# AVR_Board_4_0_FTDI_USB.net
KiCad netlist of a schematic drawn in Altium Designer
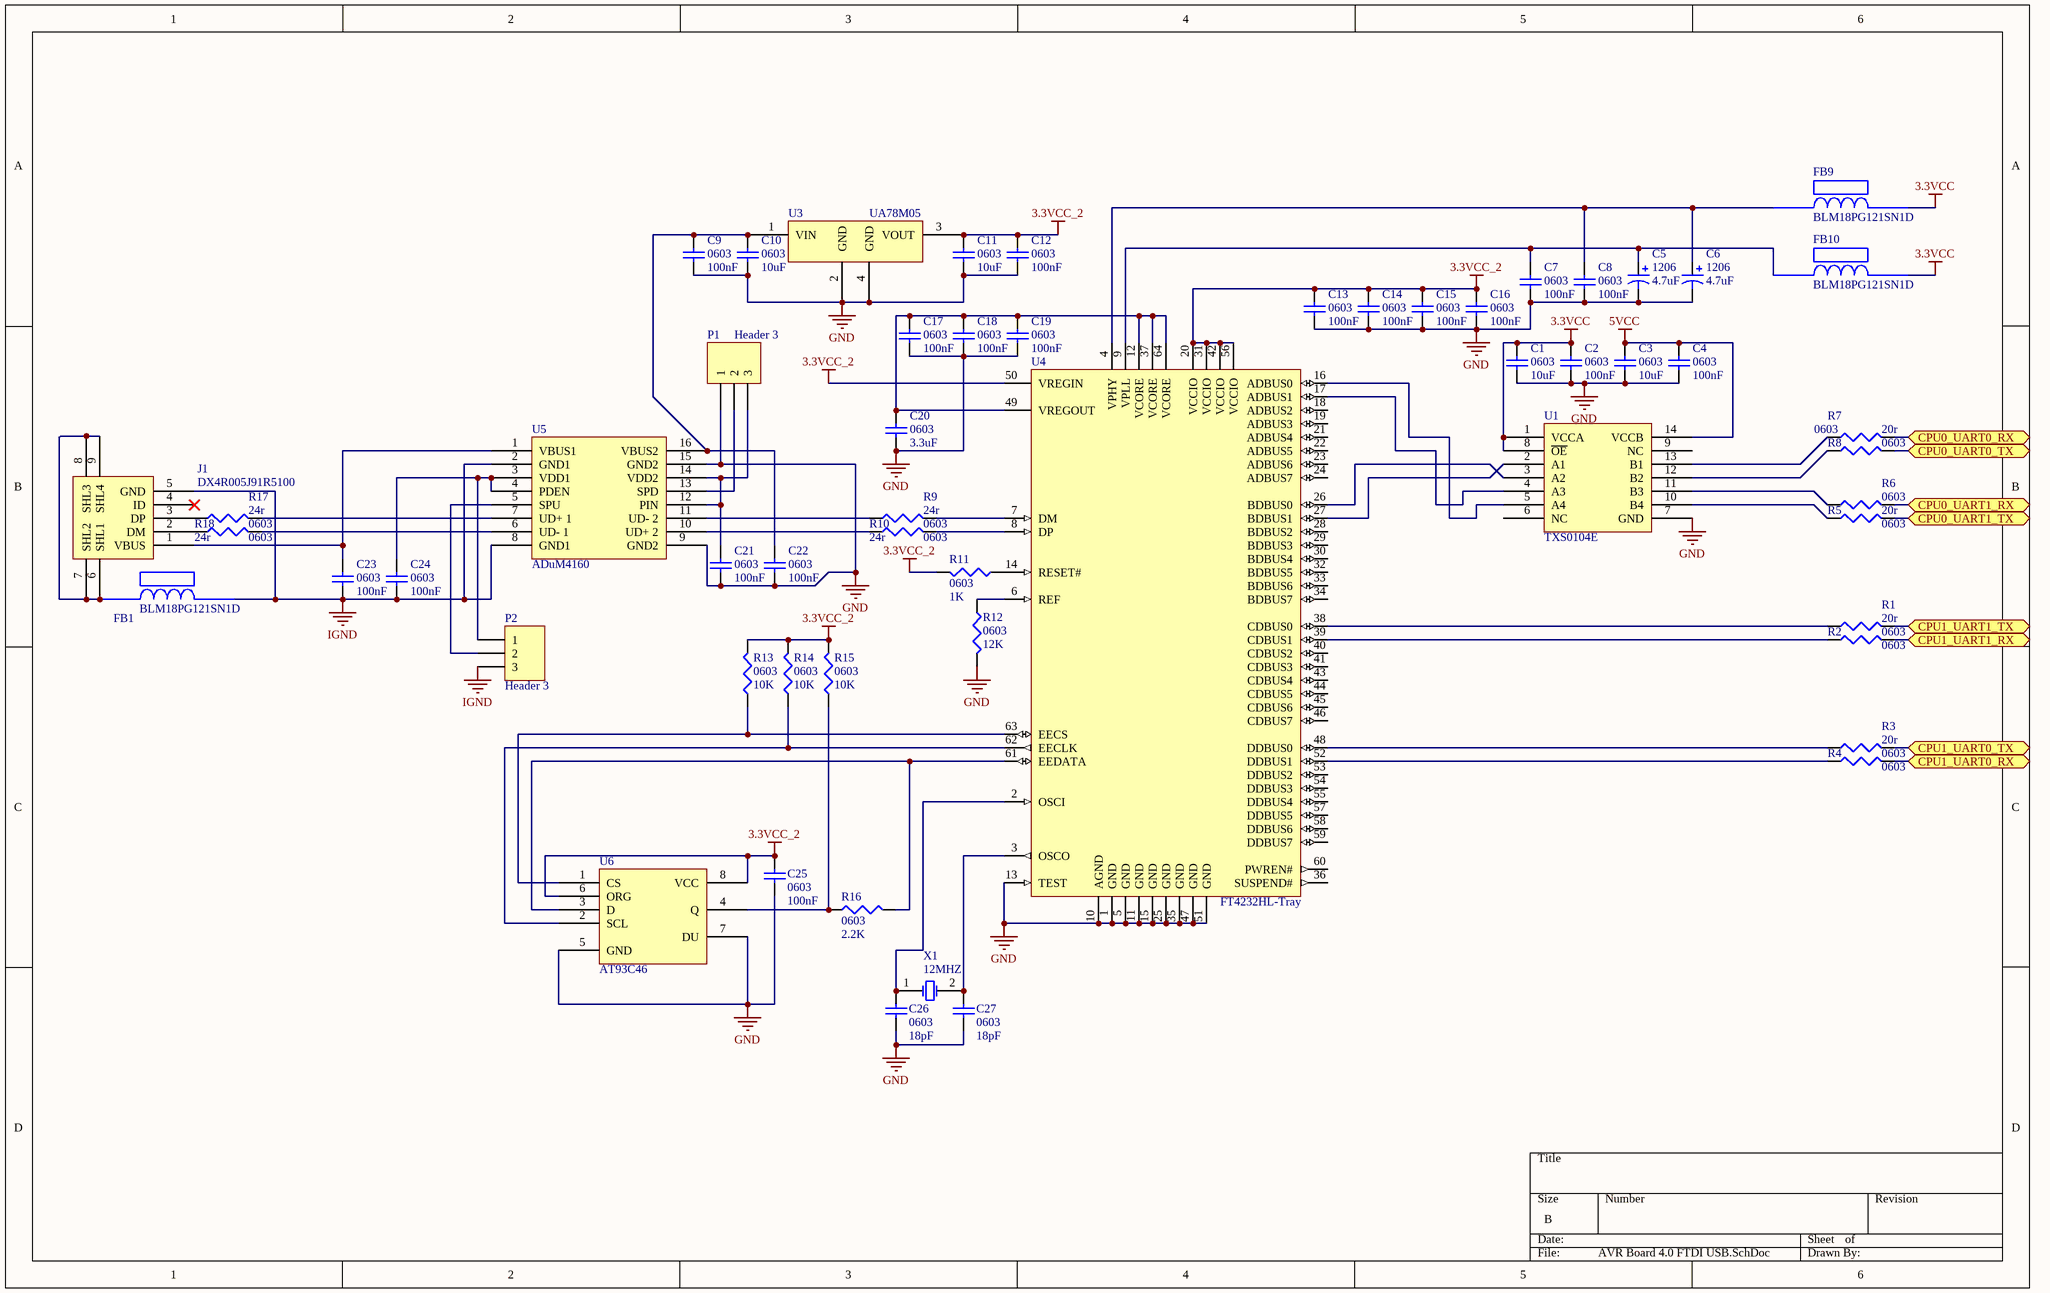
[diagram p0: AVR Board 4.0 FTDI USB.SchDoc]

(export (version "E")
  (design (tool "Eeschema 10.0.6"))
  (components
    (comp (ref "C1")
      (value "0603")
      (footprint "1608[0603]")
      (description "Capacitor (Semiconductor SIM Model)")
      (fields (field (name "ALTIUM_VALUE") "10uF") (field (name "PUBLISHER") "Altium Limited"))
      (libsource (lib "Miscellaneous Devices") (part "Cap Semi"))
    )
    (comp (ref "C2")
      (value "0603")
      (footprint "1608[0603]")
      (description "Capacitor (Semiconductor SIM Model)")
      (fields (field (name "ALTIUM_VALUE") "100nF") (field (name "PUBLISHER") "Altium Limited"))
      (libsource (lib "Miscellaneous Devices") (part "Cap Semi"))
    )
    (comp (ref "C3")
      (value "0603")
      (footprint "1608[0603]")
      (description "Capacitor (Semiconductor SIM Model)")
      (fields (field (name "ALTIUM_VALUE") "10uF") (field (name "PUBLISHER") "Altium Limited"))
      (libsource (lib "Miscellaneous Devices") (part "Cap Semi"))
    )
    (comp (ref "C4")
      (value "0603")
      (footprint "1608[0603]")
      (description "Capacitor (Semiconductor SIM Model)")
      (fields (field (name "ALTIUM_VALUE") "100nF") (field (name "PUBLISHER") "Altium Limited"))
      (libsource (lib "Miscellaneous Devices") (part "Cap Semi"))
    )
    (comp (ref "C5")
      (value "1206")
      (footprint "C1206POL")
      (description "Polarized Capacitor (Surface Mount)")
      (fields (field (name "ALTIUM_VALUE") "4.7uF") (field (name "PUBLISHER") "Altium Limited"))
      (libsource (lib "Miscellaneous Devices") (part "Cap Pol3"))
    )
    (comp (ref "C6")
      (value "1206")
      (footprint "C1206POL")
      (description "Polarized Capacitor (Surface Mount)")
      (fields (field (name "ALTIUM_VALUE") "4.7uF") (field (name "PUBLISHER") "Altium Limited"))
      (libsource (lib "Miscellaneous Devices") (part "Cap Pol3"))
    )
    (comp (ref "C7")
      (value "0603")
      (footprint "1608[0603]")
      (description "Capacitor (Semiconductor SIM Model)")
      (fields (field (name "ALTIUM_VALUE") "100nF") (field (name "PUBLISHER") "Altium Limited"))
      (libsource (lib "Miscellaneous Devices") (part "Cap Semi"))
    )
    (comp (ref "C8")
      (value "0603")
      (footprint "1608[0603]")
      (description "Capacitor (Semiconductor SIM Model)")
      (fields (field (name "ALTIUM_VALUE") "100nF") (field (name "PUBLISHER") "Altium Limited"))
      (libsource (lib "Miscellaneous Devices") (part "Cap Semi"))
    )
    (comp (ref "C9")
      (value "0603")
      (footprint "1608[0603]")
      (description "Capacitor (Semiconductor SIM Model)")
      (fields (field (name "ALTIUM_VALUE") "100nF") (field (name "PUBLISHER") "Altium Limited"))
      (libsource (lib "Miscellaneous Devices") (part "Cap Semi"))
    )
    (comp (ref "C10")
      (value "0603")
      (footprint "1608[0603]")
      (description "Capacitor (Semiconductor SIM Model)")
      (fields (field (name "ALTIUM_VALUE") "10uF") (field (name "PUBLISHER") "Altium Limited"))
      (libsource (lib "Miscellaneous Devices") (part "Cap Semi"))
    )
    (comp (ref "C11")
      (value "0603")
      (footprint "1608[0603]")
      (description "Capacitor (Semiconductor SIM Model)")
      (fields (field (name "ALTIUM_VALUE") "10uF") (field (name "PUBLISHER") "Altium Limited"))
      (libsource (lib "Miscellaneous Devices") (part "Cap Semi"))
    )
    (comp (ref "C12")
      (value "0603")
      (footprint "1608[0603]")
      (description "Capacitor (Semiconductor SIM Model)")
      (fields (field (name "ALTIUM_VALUE") "100nF") (field (name "PUBLISHER") "Altium Limited"))
      (libsource (lib "Miscellaneous Devices") (part "Cap Semi"))
    )
    (comp (ref "C13")
      (value "0603")
      (footprint "1608[0603]")
      (description "Capacitor (Semiconductor SIM Model)")
      (fields (field (name "ALTIUM_VALUE") "100nF") (field (name "PUBLISHER") "Altium Limited"))
      (libsource (lib "Miscellaneous Devices") (part "Cap Semi"))
    )
    (comp (ref "C14")
      (value "0603")
      (footprint "1608[0603]")
      (description "Capacitor (Semiconductor SIM Model)")
      (fields (field (name "ALTIUM_VALUE") "100nF") (field (name "PUBLISHER") "Altium Limited"))
      (libsource (lib "Miscellaneous Devices") (part "Cap Semi"))
    )
    (comp (ref "C15")
      (value "0603")
      (footprint "1608[0603]")
      (description "Capacitor (Semiconductor SIM Model)")
      (fields (field (name "ALTIUM_VALUE") "100nF") (field (name "PUBLISHER") "Altium Limited"))
      (libsource (lib "Miscellaneous Devices") (part "Cap Semi"))
    )
    (comp (ref "C16")
      (value "0603")
      (footprint "1608[0603]")
      (description "Capacitor (Semiconductor SIM Model)")
      (fields (field (name "ALTIUM_VALUE") "100nF") (field (name "PUBLISHER") "Altium Limited"))
      (libsource (lib "Miscellaneous Devices") (part "Cap Semi"))
    )
    (comp (ref "C17")
      (value "0603")
      (footprint "1608[0603]")
      (description "Capacitor (Semiconductor SIM Model)")
      (fields (field (name "ALTIUM_VALUE") "100nF") (field (name "PUBLISHER") "Altium Limited"))
      (libsource (lib "Miscellaneous Devices") (part "Cap Semi"))
    )
    (comp (ref "C18")
      (value "0603")
      (footprint "1608[0603]")
      (description "Capacitor (Semiconductor SIM Model)")
      (fields (field (name "ALTIUM_VALUE") "100nF") (field (name "PUBLISHER") "Altium Limited"))
      (libsource (lib "Miscellaneous Devices") (part "Cap Semi"))
    )
    (comp (ref "C19")
      (value "0603")
      (footprint "1608[0603]")
      (description "Capacitor (Semiconductor SIM Model)")
      (fields (field (name "ALTIUM_VALUE") "100nF") (field (name "PUBLISHER") "Altium Limited"))
      (libsource (lib "Miscellaneous Devices") (part "Cap Semi"))
    )
    (comp (ref "C20")
      (value "0603")
      (footprint "1608[0603]")
      (description "Capacitor (Semiconductor SIM Model)")
      (fields (field (name "ALTIUM_VALUE") "3.3uF") (field (name "PUBLISHER") "Altium Limited"))
      (libsource (lib "Miscellaneous Devices") (part "Cap Semi"))
    )
    (comp (ref "C21")
      (value "0603")
      (footprint "1608[0603]")
      (description "Capacitor (Semiconductor SIM Model)")
      (fields (field (name "ALTIUM_VALUE") "100nF") (field (name "PUBLISHER") "Altium Limited"))
      (libsource (lib "Miscellaneous Devices") (part "Cap Semi"))
    )
    (comp (ref "C22")
      (value "0603")
      (footprint "1608[0603]")
      (description "Capacitor (Semiconductor SIM Model)")
      (fields (field (name "ALTIUM_VALUE") "100nF") (field (name "PUBLISHER") "Altium Limited"))
      (libsource (lib "Miscellaneous Devices") (part "Cap Semi"))
    )
    (comp (ref "C23")
      (value "0603")
      (footprint "1608[0603]")
      (description "Capacitor (Semiconductor SIM Model)")
      (fields (field (name "ALTIUM_VALUE") "100nF") (field (name "PUBLISHER") "Altium Limited"))
      (libsource (lib "Miscellaneous Devices") (part "Cap Semi"))
    )
    (comp (ref "C24")
      (value "0603")
      (footprint "1608[0603]")
      (description "Capacitor (Semiconductor SIM Model)")
      (fields (field (name "ALTIUM_VALUE") "100nF") (field (name "PUBLISHER") "Altium Limited"))
      (libsource (lib "Miscellaneous Devices") (part "Cap Semi"))
    )
    (comp (ref "C25")
      (value "0603")
      (footprint "1608[0603]")
      (description "Capacitor (Semiconductor SIM Model)")
      (fields (field (name "ALTIUM_VALUE") "100nF") (field (name "PUBLISHER") "Altium Limited"))
      (libsource (lib "Miscellaneous Devices") (part "Cap Semi"))
    )
    (comp (ref "C26")
      (value "0603")
      (footprint "1608[0603]")
      (description "Capacitor (Semiconductor SIM Model)")
      (fields (field (name "ALTIUM_VALUE") "18pF") (field (name "PUBLISHER") "Altium Limited"))
      (libsource (lib "Miscellaneous Devices") (part "Cap Semi"))
    )
    (comp (ref "C27")
      (value "0603")
      (footprint "1608[0603]")
      (description "Capacitor (Semiconductor SIM Model)")
      (fields (field (name "ALTIUM_VALUE") "18pF") (field (name "PUBLISHER") "Altium Limited"))
      (libsource (lib "Miscellaneous Devices") (part "Cap Semi"))
    )
    (comp (ref "FB1")
      (value "BLM18PG121SN1D")
      (footprint "BLM18PG121SN1D")
      (libsource (lib "Adams Altium Library") (part "BLM18PG121SN1D"))
    )
    (comp (ref "FB9")
      (value "BLM18PG121SN1D")
      (footprint "BLM18PG121SN1D")
      (libsource (lib "Adams Altium Library") (part "BLM18PG121SN1D"))
    )
    (comp (ref "FB10")
      (value "BLM18PG121SN1D")
      (footprint "BLM18PG121SN1D")
      (libsource (lib "Adams Altium Library") (part "BLM18PG121SN1D"))
    )
    (comp (ref "J1")
      (value "DX4R005J91R5100")
      (footprint "Micro USB Circular Holes Only")
      (description "Micro USB Jack B")
      (libsource (lib "Adams Altium Library") (part "Micro USB"))
    )
    (comp (ref "P1")
      (value "Header 3")
      (footprint "HDR1X3")
      (description "Header, 3-Pin")
      (fields (field (name "PUBLISHER") "Altium Limited"))
      (libsource (lib "Miscellaneous Connectors") (part "Header 3"))
    )
    (comp (ref "P2")
      (value "Header 3")
      (footprint "HDR1X3")
      (description "Header, 3-Pin")
      (fields (field (name "PUBLISHER") "Altium Limited"))
      (libsource (lib "") (part "Header 3_1"))
    )
    (comp (ref "R1")
      (value "0603")
      (footprint "J1-0603")
      (description "Resistor")
      (fields (field (name "ALTIUM_VALUE") "20r") (field (name "PUBLISHER") "Altium Limited"))
      (libsource (lib "Miscellaneous Devices") (part "Res3"))
    )
    (comp (ref "R2")
      (value "0603")
      (footprint "J1-0603")
      (description "Resistor")
      (fields (field (name "PUBLISHER") "Altium Limited"))
      (libsource (lib "Miscellaneous Devices") (part "Res3"))
    )
    (comp (ref "R3")
      (value "0603")
      (footprint "J1-0603")
      (description "Resistor")
      (fields (field (name "ALTIUM_VALUE") "20r") (field (name "PUBLISHER") "Altium Limited"))
      (libsource (lib "Miscellaneous Devices") (part "Res3"))
    )
    (comp (ref "R4")
      (value "0603")
      (footprint "J1-0603")
      (description "Resistor")
      (fields (field (name "PUBLISHER") "Altium Limited"))
      (libsource (lib "Miscellaneous Devices") (part "Res3"))
    )
    (comp (ref "R5")
      (value "0603")
      (footprint "J1-0603")
      (description "Resistor")
      (fields (field (name "ALTIUM_VALUE") "20r") (field (name "PUBLISHER") "Altium Limited"))
      (libsource (lib "Miscellaneous Devices") (part "Res3"))
    )
    (comp (ref "R6")
      (value "0603")
      (footprint "J1-0603")
      (description "Resistor")
      (fields (field (name "PUBLISHER") "Altium Limited"))
      (libsource (lib "Miscellaneous Devices") (part "Res3"))
    )
    (comp (ref "R7")
      (value "0603")
      (footprint "J1-0603")
      (description "Resistor")
      (fields (field (name "ALTIUM_VALUE") "20r") (field (name "PUBLISHER") "Altium Limited"))
      (libsource (lib "Miscellaneous Devices") (part "Res3"))
    )
    (comp (ref "R8")
      (value "0603")
      (footprint "J1-0603")
      (description "Resistor")
      (fields (field (name "PUBLISHER") "Altium Limited"))
      (libsource (lib "Miscellaneous Devices") (part "Res3"))
    )
    (comp (ref "R9")
      (value "0603")
      (footprint "J1-0603")
      (description "Resistor")
      (fields (field (name "ALTIUM_VALUE") "24r") (field (name "PUBLISHER") "Altium Limited"))
      (libsource (lib "Miscellaneous Devices") (part "Res3"))
    )
    (comp (ref "R10")
      (value "0603")
      (footprint "J1-0603")
      (description "Resistor")
      (fields (field (name "ALTIUM_VALUE") "24r") (field (name "PUBLISHER") "Altium Limited"))
      (libsource (lib "Miscellaneous Devices") (part "Res3"))
    )
    (comp (ref "R11")
      (value "0603")
      (footprint "J1-0603")
      (description "Resistor")
      (fields (field (name "ALTIUM_VALUE") "1K") (field (name "PUBLISHER") "Altium Limited"))
      (libsource (lib "Miscellaneous Devices") (part "Res3"))
    )
    (comp (ref "R12")
      (value "0603")
      (footprint "J1-0603")
      (description "Resistor")
      (fields (field (name "ALTIUM_VALUE") "12K") (field (name "PUBLISHER") "Altium Limited"))
      (libsource (lib "Miscellaneous Devices") (part "Res3"))
    )
    (comp (ref "R13")
      (value "0603")
      (footprint "J1-0603")
      (description "Resistor")
      (fields (field (name "ALTIUM_VALUE") "10K") (field (name "PUBLISHER") "Altium Limited"))
      (libsource (lib "Miscellaneous Devices") (part "Res3"))
    )
    (comp (ref "R14")
      (value "0603")
      (footprint "J1-0603")
      (description "Resistor")
      (fields (field (name "ALTIUM_VALUE") "10K") (field (name "PUBLISHER") "Altium Limited"))
      (libsource (lib "Miscellaneous Devices") (part "Res3"))
    )
    (comp (ref "R15")
      (value "0603")
      (footprint "J1-0603")
      (description "Resistor")
      (fields (field (name "ALTIUM_VALUE") "10K") (field (name "PUBLISHER") "Altium Limited"))
      (libsource (lib "Miscellaneous Devices") (part "Res3"))
    )
    (comp (ref "R16")
      (value "0603")
      (footprint "J1-0603")
      (description "Resistor")
      (fields (field (name "ALTIUM_VALUE") "2.2K") (field (name "PUBLISHER") "Altium Limited"))
      (libsource (lib "Miscellaneous Devices") (part "Res3"))
    )
    (comp (ref "R17")
      (value "0603")
      (footprint "J1-0603")
      (description "Resistor")
      (fields (field (name "ALTIUM_VALUE") "24r") (field (name "PUBLISHER") "Altium Limited"))
      (libsource (lib "Miscellaneous Devices") (part "Res3"))
    )
    (comp (ref "R18")
      (value "0603")
      (footprint "J1-0603")
      (description "Resistor")
      (fields (field (name "ALTIUM_VALUE") "24r") (field (name "PUBLISHER") "Altium Limited"))
      (libsource (lib "Miscellaneous Devices") (part "Res3"))
    )
    (comp (ref "U1")
      (value "TXS0104E")
      (footprint "SOIC127P600X175-14N")
      (libsource (lib "AVR Board 4.0 Symbol Lib") (part "TXS0104E"))
    )
    (comp (ref "U3")
      (value "UA78M05")
      (footprint "SOT230P700X180-4N")
      (libsource (lib "AVR Board 4.0 Symbol Lib") (part "UA78M05"))
    )
    (comp (ref "U4")
      (value "FT4232HL-Tray")
      (footprint "LQFP-64_N")
      (description "Quad High Speed USB To Multipurpose UART/MPSSE IC, 64-pin LQFP, Tray")
      (fields (field (name "MANUFACTURER") "FTDI"))
      (libsource (lib "FTDI FT Series") (part "FT4232HL-Tray"))
    )
    (comp (ref "U5")
      (value "ADuM4160")
      (footprint "ADuM4160")
      (description "USB Opto Isolator")
      (libsource (lib "AVR Board 4.0 Symbol Lib") (part "ADuM4160"))
    )
    (comp (ref "U6")
      (value "AT93C46")
      (footprint "SOIC127P600X175-8N")
      (libsource (lib "AVR Board 4.0 Symbol Lib") (part "AT93C46"))
    )
    (comp (ref "X1")
      (value "12MHZ")
      (footprint "445C35A12M00000")
      (description "Crystal Oscillator")
      (fields (field (name "PUBLISHER") "Altium Limited"))
      (libsource (lib "Miscellaneous Devices") (part "XTAL"))
    )
  )
  (nets
    (net (code "1") (name "/CPU0_UART0_RX") (class "Default")
      (node (ref "R7") (pin "2") (pinfunction "2_2") (pintype "passive"))
    )
    (net (code "2") (name "/CPU0_UART0_TX") (class "Default")
      (node (ref "R8") (pin "2") (pinfunction "2_2") (pintype "passive"))
    )
    (net (code "3") (name "/CPU0_UART1_RX") (class "Default")
      (node (ref "R6") (pin "2") (pinfunction "2_2") (pintype "passive"))
    )
    (net (code "4") (name "/CPU0_UART1_TX") (class "Default")
      (node (ref "R5") (pin "2") (pinfunction "2_2") (pintype "passive"))
    )
    (net (code "5") (name "/CPU1_UART0_RX") (class "Default")
      (node (ref "R4") (pin "2") (pinfunction "2_2") (pintype "passive"))
    )
    (net (code "6") (name "/CPU1_UART0_TX") (class "Default")
      (node (ref "R3") (pin "2") (pinfunction "2_2") (pintype "passive"))
    )
    (net (code "7") (name "/CPU1_UART1_RX") (class "Default")
      (node (ref "R2") (pin "2") (pinfunction "2_2") (pintype "passive"))
    )
    (net (code "8") (name "/CPU1_UART1_TX") (class "Default")
      (node (ref "R1") (pin "2") (pinfunction "2_2") (pintype "passive"))
    )
    (net (code "9") (name "3.3VCC") (class "Default")
      (node (ref "C1") (pin "2") (pinfunction "2_2") (pintype "passive"))
      (node (ref "C2") (pin "2") (pinfunction "2_2") (pintype "passive"))
      (node (ref "FB10") (pin "2") (pinfunction "2_2") (pintype "passive"))
      (node (ref "FB9") (pin "2") (pinfunction "2_2") (pintype "passive"))
      (node (ref "U1") (pin "1") (pinfunction "VCCA_1") (pintype "passive"))
      (node (ref "U1") (pin "8") (pinfunction "~{OE}_8") (pintype "passive"))
    )
    (net (code "10") (name "3.3VCC_2") (class "Default")
      (node (ref "C11") (pin "2") (pinfunction "2_2") (pintype "passive"))
      (node (ref "C12") (pin "2") (pinfunction "2_2") (pintype "passive"))
      (node (ref "C13") (pin "2") (pinfunction "2_2") (pintype "passive"))
      (node (ref "C14") (pin "2") (pinfunction "2_2") (pintype "passive"))
      (node (ref "C15") (pin "2") (pinfunction "2_2") (pintype "passive"))
      (node (ref "C16") (pin "2") (pinfunction "2_2") (pintype "passive"))
      (node (ref "C25") (pin "2") (pinfunction "2_2") (pintype "passive"))
      (node (ref "R11") (pin "2") (pinfunction "2_2") (pintype "passive"))
      (node (ref "R13") (pin "2") (pinfunction "2_2") (pintype "passive"))
      (node (ref "R14") (pin "2") (pinfunction "2_2") (pintype "passive"))
      (node (ref "R15") (pin "2") (pinfunction "2_2") (pintype "passive"))
      (node (ref "U3") (pin "3") (pinfunction "VOUT_3") (pintype "passive"))
      (node (ref "U4") (pin "20") (pinfunction "VCCIO_20") (pintype "power_in"))
      (node (ref "U4") (pin "31") (pinfunction "VCCIO_31") (pintype "power_in"))
      (node (ref "U4") (pin "42") (pinfunction "VCCIO_42") (pintype "power_in"))
      (node (ref "U4") (pin "50") (pinfunction "VREGIN_50") (pintype "power_in"))
      (node (ref "U4") (pin "56") (pinfunction "VCCIO_56") (pintype "power_in"))
      (node (ref "U6") (pin "6") (pinfunction "ORG_6") (pintype "passive"))
      (node (ref "U6") (pin "8") (pinfunction "VCC_8") (pintype "passive"))
    )
    (net (code "11") (name "5VCC") (class "Default")
      (node (ref "C3") (pin "2") (pinfunction "2_2") (pintype "passive"))
      (node (ref "C4") (pin "2") (pinfunction "2_2") (pintype "passive"))
      (node (ref "U1") (pin "14") (pinfunction "VCCB_14") (pintype "passive"))
    )
    (net (code "12") (name "GND") (class "Default")
      (node (ref "C1") (pin "1") (pinfunction "1_1") (pintype "passive"))
      (node (ref "C10") (pin "1") (pinfunction "1_1") (pintype "passive"))
      (node (ref "C11") (pin "1") (pinfunction "1_1") (pintype "passive"))
      (node (ref "C12") (pin "1") (pinfunction "1_1") (pintype "passive"))
      (node (ref "C13") (pin "1") (pinfunction "1_1") (pintype "passive"))
      (node (ref "C14") (pin "1") (pinfunction "1_1") (pintype "passive"))
      (node (ref "C15") (pin "1") (pinfunction "1_1") (pintype "passive"))
      (node (ref "C16") (pin "1") (pinfunction "1_1") (pintype "passive"))
      (node (ref "C17") (pin "1") (pinfunction "1_1") (pintype "passive"))
      (node (ref "C18") (pin "1") (pinfunction "1_1") (pintype "passive"))
      (node (ref "C19") (pin "1") (pinfunction "1_1") (pintype "passive"))
      (node (ref "C2") (pin "1") (pinfunction "1_1") (pintype "passive"))
      (node (ref "C20") (pin "1") (pinfunction "1_1") (pintype "passive"))
      (node (ref "C21") (pin "1") (pinfunction "1_1") (pintype "passive"))
      (node (ref "C22") (pin "1") (pinfunction "1_1") (pintype "passive"))
      (node (ref "C25") (pin "1") (pinfunction "1_1") (pintype "passive"))
      (node (ref "C26") (pin "1") (pinfunction "1_1") (pintype "passive"))
      (node (ref "C27") (pin "1") (pinfunction "1_1") (pintype "passive"))
      (node (ref "C3") (pin "1") (pinfunction "1_1") (pintype "passive"))
      (node (ref "C4") (pin "1") (pinfunction "1_1") (pintype "passive"))
      (node (ref "C5") (pin "2") (pinfunction "2_2") (pintype "passive"))
      (node (ref "C6") (pin "2") (pinfunction "2_2") (pintype "passive"))
      (node (ref "C7") (pin "1") (pinfunction "1_1") (pintype "passive"))
      (node (ref "C8") (pin "1") (pinfunction "1_1") (pintype "passive"))
      (node (ref "C9") (pin "1") (pinfunction "1_1") (pintype "passive"))
      (node (ref "P1") (pin "1") (pinfunction "1_1") (pintype "passive"))
      (node (ref "R12") (pin "2") (pinfunction "2_2") (pintype "passive"))
      (node (ref "U1") (pin "7") (pinfunction "GND_7") (pintype "passive"))
      (node (ref "U3") (pin "2") (pinfunction "GND_2") (pintype "passive"))
      (node (ref "U3") (pin "4") (pinfunction "GND_4") (pintype "passive"))
      (node (ref "U4") (pin "1") (pinfunction "GND_1") (pintype "power_in"))
      (node (ref "U4") (pin "10") (pinfunction "AGND_10") (pintype "power_in"))
      (node (ref "U4") (pin "11") (pinfunction "GND_11") (pintype "power_in"))
      (node (ref "U4") (pin "13") (pinfunction "TEST_13") (pintype "input"))
      (node (ref "U4") (pin "15") (pinfunction "GND_15") (pintype "power_in"))
      (node (ref "U4") (pin "25") (pinfunction "GND_25") (pintype "power_in"))
      (node (ref "U4") (pin "35") (pinfunction "GND_35") (pintype "power_in"))
      (node (ref "U4") (pin "47") (pinfunction "GND_47") (pintype "power_in"))
      (node (ref "U4") (pin "5") (pinfunction "GND_5") (pintype "power_in"))
      (node (ref "U4") (pin "51") (pinfunction "GND_51") (pintype "power_in"))
      (node (ref "U5") (pin "15") (pinfunction "GND2_15") (pintype "passive"))
      (node (ref "U5") (pin "9") (pinfunction "GND2_9") (pintype "passive"))
      (node (ref "U6") (pin "5") (pinfunction "GND_5") (pintype "passive"))
      (node (ref "U6") (pin "7") (pinfunction "DU_7") (pintype "passive"))
    )
    (net (code "13") (name "IGND") (class "Default")
      (node (ref "C23") (pin "1") (pinfunction "1_1") (pintype "passive"))
      (node (ref "C24") (pin "1") (pinfunction "1_1") (pintype "passive"))
      (node (ref "FB1") (pin "2") (pinfunction "2_2") (pintype "passive"))
      (node (ref "J1") (pin "5") (pinfunction "GND_5") (pintype "passive"))
      (node (ref "P2") (pin "3") (pinfunction "3_3") (pintype "passive"))
      (node (ref "U5") (pin "2") (pinfunction "GND1_2") (pintype "passive"))
      (node (ref "U5") (pin "8") (pinfunction "GND1_8") (pintype "passive"))
    )
    (net (code "14") (name "Net-(J1-DM)") (class "Default")
      (node (ref "J1") (pin "2") (pinfunction "DM_2") (pintype "passive"))
      (node (ref "R18") (pin "1") (pinfunction "1_1") (pintype "passive"))
    )
    (net (code "15") (name "Net-(J1-DP)") (class "Default")
      (node (ref "J1") (pin "3") (pinfunction "DP_3") (pintype "passive"))
      (node (ref "R17") (pin "1") (pinfunction "1_1") (pintype "passive"))
    )
    (net (code "16") (name "Net-(J1-SHL1)") (class "Default")
      (node (ref "FB1") (pin "1") (pinfunction "1_1") (pintype "passive"))
      (node (ref "J1") (pin "6") (pinfunction "SHL1_6") (pintype "passive"))
      (node (ref "J1") (pin "7") (pinfunction "SHL2_7") (pintype "passive"))
      (node (ref "J1") (pin "8") (pinfunction "SHL3_8") (pintype "passive"))
      (node (ref "J1") (pin "9") (pinfunction "SHL4_9") (pintype "passive"))
    )
    (net (code "17") (name "Net-(J1-VBUS)") (class "Default")
      (node (ref "C23") (pin "2") (pinfunction "2_2") (pintype "passive"))
      (node (ref "J1") (pin "1") (pinfunction "VBUS_1") (pintype "passive"))
      (node (ref "U5") (pin "1") (pinfunction "VBUS1_1") (pintype "passive"))
    )
    (net (code "18") (name "Net-(U1-A1)") (class "Default")
      (node (ref "U1") (pin "2") (pinfunction "A1_2") (pintype "passive"))
      (node (ref "U4") (pin "27") (pinfunction "BDBUS1_27") (pintype "bidirectional"))
    )
    (net (code "19") (name "Net-(U1-A2)") (class "Default")
      (node (ref "U1") (pin "3") (pinfunction "A2_3") (pintype "passive"))
      (node (ref "U4") (pin "26") (pinfunction "BDBUS0_26") (pintype "bidirectional"))
    )
    (net (code "20") (name "Net-(U1-A3)") (class "Default")
      (node (ref "U1") (pin "4") (pinfunction "A3_4") (pintype "passive"))
      (node (ref "U4") (pin "17") (pinfunction "ADBUS1_17") (pintype "bidirectional"))
    )
    (net (code "21") (name "Net-(U1-A4)") (class "Default")
      (node (ref "U1") (pin "5") (pinfunction "A4_5") (pintype "passive"))
      (node (ref "U4") (pin "16") (pinfunction "ADBUS0_16") (pintype "bidirectional"))
    )
    (net (code "22") (name "Net-(U1-B1)") (class "Default")
      (node (ref "R7") (pin "1") (pinfunction "1_1") (pintype "passive"))
      (node (ref "U1") (pin "13") (pinfunction "B1_13") (pintype "passive"))
    )
    (net (code "23") (name "Net-(U1-B2)") (class "Default")
      (node (ref "R8") (pin "1") (pinfunction "1_1") (pintype "passive"))
      (node (ref "U1") (pin "12") (pinfunction "B2_12") (pintype "passive"))
    )
    (net (code "24") (name "Net-(U1-B3)") (class "Default")
      (node (ref "R6") (pin "1") (pinfunction "1_1") (pintype "passive"))
      (node (ref "U1") (pin "11") (pinfunction "B3_11") (pintype "passive"))
    )
    (net (code "25") (name "Net-(U1-B4)") (class "Default")
      (node (ref "R5") (pin "1") (pinfunction "1_1") (pintype "passive"))
      (node (ref "U1") (pin "10") (pinfunction "B4_10") (pintype "passive"))
    )
    (net (code "26") (name "Net-(U3-VIN)") (class "Default")
      (node (ref "C10") (pin "2") (pinfunction "2_2") (pintype "passive"))
      (node (ref "C22") (pin "2") (pinfunction "2_2") (pintype "passive"))
      (node (ref "C9") (pin "2") (pinfunction "2_2") (pintype "passive"))
      (node (ref "U3") (pin "1") (pinfunction "VIN_1") (pintype "passive"))
      (node (ref "U5") (pin "16") (pinfunction "VBUS2_16") (pintype "passive"))
    )
    (net (code "27") (name "Net-(U4-CDBUS0)") (class "Default")
      (node (ref "R1") (pin "1") (pinfunction "1_1") (pintype "passive"))
      (node (ref "U4") (pin "38") (pinfunction "CDBUS0_38") (pintype "bidirectional"))
    )
    (net (code "28") (name "Net-(U4-CDBUS1)") (class "Default")
      (node (ref "R2") (pin "1") (pinfunction "1_1") (pintype "passive"))
      (node (ref "U4") (pin "39") (pinfunction "CDBUS1_39") (pintype "bidirectional"))
    )
    (net (code "29") (name "Net-(U4-DDBUS0)") (class "Default")
      (node (ref "R3") (pin "1") (pinfunction "1_1") (pintype "passive"))
      (node (ref "U4") (pin "48") (pinfunction "DDBUS0_48") (pintype "bidirectional"))
    )
    (net (code "30") (name "Net-(U4-DDBUS1)") (class "Default")
      (node (ref "R4") (pin "1") (pinfunction "1_1") (pintype "passive"))
      (node (ref "U4") (pin "52") (pinfunction "DDBUS1_52") (pintype "bidirectional"))
    )
    (net (code "31") (name "Net-(U4-DM)") (class "Default")
      (node (ref "R9") (pin "2") (pinfunction "2_2") (pintype "passive"))
      (node (ref "U4") (pin "7") (pinfunction "DM_7") (pintype "input"))
    )
    (net (code "32") (name "Net-(U4-DP)") (class "Default")
      (node (ref "R10") (pin "2") (pinfunction "2_2") (pintype "passive"))
      (node (ref "U4") (pin "8") (pinfunction "DP_8") (pintype "input"))
    )
    (net (code "33") (name "Net-(U4-EECLK)") (class "Default")
      (node (ref "R14") (pin "1") (pinfunction "1_1") (pintype "passive"))
      (node (ref "U4") (pin "62") (pinfunction "EECLK_62") (pintype "output"))
      (node (ref "U6") (pin "2") (pinfunction "SCL_2") (pintype "passive"))
    )
    (net (code "34") (name "Net-(U4-EECS)") (class "Default")
      (node (ref "R13") (pin "1") (pinfunction "1_1") (pintype "passive"))
      (node (ref "U4") (pin "63") (pinfunction "EECS_63") (pintype "bidirectional"))
      (node (ref "U6") (pin "1") (pinfunction "CS_1") (pintype "passive"))
    )
    (net (code "35") (name "Net-(U4-EEDATA)") (class "Default")
      (node (ref "R16") (pin "2") (pinfunction "2_2") (pintype "passive"))
      (node (ref "U4") (pin "61") (pinfunction "EEDATA_61") (pintype "bidirectional"))
      (node (ref "U6") (pin "3") (pinfunction "D_3") (pintype "passive"))
    )
    (net (code "36") (name "Net-(U4-OSCI)") (class "Default")
      (node (ref "C26") (pin "2") (pinfunction "2_2") (pintype "passive"))
      (node (ref "U4") (pin "2") (pinfunction "OSCI_2") (pintype "input"))
      (node (ref "X1") (pin "1") (pinfunction "OSC1_1") (pintype "passive"))
    )
    (net (code "37") (name "Net-(U4-OSCO)") (class "Default")
      (node (ref "C27") (pin "2") (pinfunction "2_2") (pintype "passive"))
      (node (ref "U4") (pin "3") (pinfunction "OSCO_3") (pintype "output"))
      (node (ref "X1") (pin "2") (pinfunction "OSC2_2") (pintype "passive"))
    )
    (net (code "38") (name "Net-(U4-REF)") (class "Default")
      (node (ref "R12") (pin "1") (pinfunction "1_1") (pintype "passive"))
      (node (ref "U4") (pin "6") (pinfunction "REF_6") (pintype "input"))
    )
    (net (code "39") (name "Net-(U4-RESET#)") (class "Default")
      (node (ref "R11") (pin "1") (pinfunction "1_1") (pintype "passive"))
      (node (ref "U4") (pin "14") (pinfunction "RESET#_14") (pintype "input"))
    )
    (net (code "40") (name "Net-(U4-VPHY)") (class "Default")
      (node (ref "C6") (pin "1") (pinfunction "1_1") (pintype "passive"))
      (node (ref "C8") (pin "2") (pinfunction "2_2") (pintype "passive"))
      (node (ref "FB9") (pin "1") (pinfunction "1_1") (pintype "passive"))
      (node (ref "U4") (pin "4") (pinfunction "VPHY_4") (pintype "power_in"))
    )
    (net (code "41") (name "Net-(U4-VPLL)") (class "Default")
      (node (ref "C5") (pin "1") (pinfunction "1_1") (pintype "passive"))
      (node (ref "C7") (pin "2") (pinfunction "2_2") (pintype "passive"))
      (node (ref "FB10") (pin "1") (pinfunction "1_1") (pintype "passive"))
      (node (ref "U4") (pin "9") (pinfunction "VPLL_9") (pintype "power_in"))
    )
    (net (code "42") (name "Net-(U4-VREGOUT)") (class "Default")
      (node (ref "C17") (pin "2") (pinfunction "2_2") (pintype "passive"))
      (node (ref "C18") (pin "2") (pinfunction "2_2") (pintype "passive"))
      (node (ref "C19") (pin "2") (pinfunction "2_2") (pintype "passive"))
      (node (ref "C20") (pin "2") (pinfunction "2_2") (pintype "passive"))
      (node (ref "U4") (pin "12") (pinfunction "VCORE_12") (pintype "power_in"))
      (node (ref "U4") (pin "37") (pinfunction "VCORE_37") (pintype "power_in"))
      (node (ref "U4") (pin "49") (pinfunction "VREGOUT_49") (pintype "power_in"))
      (node (ref "U4") (pin "64") (pinfunction "VCORE_64") (pintype "power_in"))
    )
    (net (code "43") (name "Net-(U5-PDEN)") (class "Default")
      (node (ref "C24") (pin "2") (pinfunction "2_2") (pintype "passive"))
      (node (ref "P2") (pin "1") (pinfunction "1_1") (pintype "passive"))
      (node (ref "U5") (pin "3") (pinfunction "VDD1_3") (pintype "passive"))
      (node (ref "U5") (pin "4") (pinfunction "PDEN_4") (pintype "passive"))
    )
    (net (code "44") (name "Net-(U5-PIN)") (class "Default")
      (node (ref "C21") (pin "2") (pinfunction "2_2") (pintype "passive"))
      (node (ref "P1") (pin "3") (pinfunction "3_3") (pintype "passive"))
      (node (ref "U5") (pin "12") (pinfunction "PIN_12") (pintype "passive"))
      (node (ref "U5") (pin "14") (pinfunction "VDD2_14") (pintype "passive"))
    )
    (net (code "45") (name "Net-(U5-SPD)") (class "Default")
      (node (ref "P1") (pin "2") (pinfunction "2_2") (pintype "passive"))
      (node (ref "U5") (pin "13") (pinfunction "SPD_13") (pintype "passive"))
    )
    (net (code "46") (name "Net-(U5-SPU)") (class "Default")
      (node (ref "P2") (pin "2") (pinfunction "2_2") (pintype "passive"))
      (node (ref "U5") (pin "5") (pinfunction "SPU_5") (pintype "passive"))
    )
    (net (code "47") (name "Net-(U5-UD+_1)") (class "Default")
      (node (ref "R17") (pin "2") (pinfunction "2_2") (pintype "passive"))
      (node (ref "U5") (pin "7") (pinfunction "UD+_1_7") (pintype "passive"))
    )
    (net (code "48") (name "Net-(U5-UD+_2)") (class "Default")
      (node (ref "R10") (pin "1") (pinfunction "1_1") (pintype "passive"))
      (node (ref "U5") (pin "10") (pinfunction "UD+_2_10") (pintype "passive"))
    )
    (net (code "49") (name "Net-(U5-UD-_1)") (class "Default")
      (node (ref "R18") (pin "2") (pinfunction "2_2") (pintype "passive"))
      (node (ref "U5") (pin "6") (pinfunction "UD-_1_6") (pintype "passive"))
    )
    (net (code "50") (name "Net-(U5-UD-_2)") (class "Default")
      (node (ref "R9") (pin "1") (pinfunction "1_1") (pintype "passive"))
      (node (ref "U5") (pin "11") (pinfunction "UD-_2_11") (pintype "passive"))
    )
    (net (code "51") (name "Net-(U6-Q)") (class "Default")
      (node (ref "R15") (pin "1") (pinfunction "1_1") (pintype "passive"))
      (node (ref "R16") (pin "1") (pinfunction "1_1") (pintype "passive"))
      (node (ref "U6") (pin "4") (pinfunction "Q_4") (pintype "passive"))
    )
    (net (code "52") (name "unconnected-(J1-ID-Pad4)") (class "Default")
      (node (ref "J1") (pin "4") (pinfunction "ID_4") (pintype "passive+no_connect"))
    )
    (net (code "53") (name "unconnected-(U1-NC-Pad6)") (class "Default")
      (node (ref "U1") (pin "6") (pinfunction "NC_6") (pintype "passive"))
    )
    (net (code "54") (name "unconnected-(U1-NC-Pad9)") (class "Default")
      (node (ref "U1") (pin "9") (pinfunction "NC_9") (pintype "passive"))
    )
    (net (code "55") (name "unconnected-(U4-ADBUS2-Pad18)") (class "Default")
      (node (ref "U4") (pin "18") (pinfunction "ADBUS2_18") (pintype "bidirectional"))
    )
    (net (code "56") (name "unconnected-(U4-ADBUS3-Pad19)") (class "Default")
      (node (ref "U4") (pin "19") (pinfunction "ADBUS3_19") (pintype "bidirectional"))
    )
    (net (code "57") (name "unconnected-(U4-ADBUS4-Pad21)") (class "Default")
      (node (ref "U4") (pin "21") (pinfunction "ADBUS4_21") (pintype "bidirectional"))
    )
    (net (code "58") (name "unconnected-(U4-ADBUS5-Pad22)") (class "Default")
      (node (ref "U4") (pin "22") (pinfunction "ADBUS5_22") (pintype "bidirectional"))
    )
    (net (code "59") (name "unconnected-(U4-ADBUS6-Pad23)") (class "Default")
      (node (ref "U4") (pin "23") (pinfunction "ADBUS6_23") (pintype "bidirectional"))
    )
    (net (code "60") (name "unconnected-(U4-ADBUS7-Pad24)") (class "Default")
      (node (ref "U4") (pin "24") (pinfunction "ADBUS7_24") (pintype "bidirectional"))
    )
    (net (code "61") (name "unconnected-(U4-BDBUS2-Pad28)") (class "Default")
      (node (ref "U4") (pin "28") (pinfunction "BDBUS2_28") (pintype "bidirectional"))
    )
    (net (code "62") (name "unconnected-(U4-BDBUS3-Pad29)") (class "Default")
      (node (ref "U4") (pin "29") (pinfunction "BDBUS3_29") (pintype "bidirectional"))
    )
    (net (code "63") (name "unconnected-(U4-BDBUS4-Pad30)") (class "Default")
      (node (ref "U4") (pin "30") (pinfunction "BDBUS4_30") (pintype "bidirectional"))
    )
    (net (code "64") (name "unconnected-(U4-BDBUS5-Pad32)") (class "Default")
      (node (ref "U4") (pin "32") (pinfunction "BDBUS5_32") (pintype "bidirectional"))
    )
    (net (code "65") (name "unconnected-(U4-BDBUS6-Pad33)") (class "Default")
      (node (ref "U4") (pin "33") (pinfunction "BDBUS6_33") (pintype "bidirectional"))
    )
    (net (code "66") (name "unconnected-(U4-BDBUS7-Pad34)") (class "Default")
      (node (ref "U4") (pin "34") (pinfunction "BDBUS7_34") (pintype "bidirectional"))
    )
    (net (code "67") (name "unconnected-(U4-CDBUS2-Pad40)") (class "Default")
      (node (ref "U4") (pin "40") (pinfunction "CDBUS2_40") (pintype "bidirectional"))
    )
    (net (code "68") (name "unconnected-(U4-CDBUS3-Pad41)") (class "Default")
      (node (ref "U4") (pin "41") (pinfunction "CDBUS3_41") (pintype "bidirectional"))
    )
    (net (code "69") (name "unconnected-(U4-CDBUS4-Pad43)") (class "Default")
      (node (ref "U4") (pin "43") (pinfunction "CDBUS4_43") (pintype "bidirectional"))
    )
    (net (code "70") (name "unconnected-(U4-CDBUS5-Pad44)") (class "Default")
      (node (ref "U4") (pin "44") (pinfunction "CDBUS5_44") (pintype "bidirectional"))
    )
    (net (code "71") (name "unconnected-(U4-CDBUS6-Pad45)") (class "Default")
      (node (ref "U4") (pin "45") (pinfunction "CDBUS6_45") (pintype "bidirectional"))
    )
    (net (code "72") (name "unconnected-(U4-CDBUS7-Pad46)") (class "Default")
      (node (ref "U4") (pin "46") (pinfunction "CDBUS7_46") (pintype "bidirectional"))
    )
    (net (code "73") (name "unconnected-(U4-DDBUS2-Pad53)") (class "Default")
      (node (ref "U4") (pin "53") (pinfunction "DDBUS2_53") (pintype "bidirectional"))
    )
    (net (code "74") (name "unconnected-(U4-DDBUS3-Pad54)") (class "Default")
      (node (ref "U4") (pin "54") (pinfunction "DDBUS3_54") (pintype "bidirectional"))
    )
    (net (code "75") (name "unconnected-(U4-DDBUS4-Pad55)") (class "Default")
      (node (ref "U4") (pin "55") (pinfunction "DDBUS4_55") (pintype "bidirectional"))
    )
    (net (code "76") (name "unconnected-(U4-DDBUS5-Pad57)") (class "Default")
      (node (ref "U4") (pin "57") (pinfunction "DDBUS5_57") (pintype "bidirectional"))
    )
    (net (code "77") (name "unconnected-(U4-DDBUS6-Pad58)") (class "Default")
      (node (ref "U4") (pin "58") (pinfunction "DDBUS6_58") (pintype "bidirectional"))
    )
    (net (code "78") (name "unconnected-(U4-DDBUS7-Pad59)") (class "Default")
      (node (ref "U4") (pin "59") (pinfunction "DDBUS7_59") (pintype "bidirectional"))
    )
    (net (code "79") (name "unconnected-(U4-PWREN#-Pad60)") (class "Default")
      (node (ref "U4") (pin "60") (pinfunction "PWREN#_60") (pintype "output"))
    )
    (net (code "80") (name "unconnected-(U4-SUSPEND#-Pad36)") (class "Default")
      (node (ref "U4") (pin "36") (pinfunction "SUSPEND#_36") (pintype "output"))
    )
  )
)
